# LvpeclTermWithCtrl.net
KiCad netlist of a schematic drawn in Altium Designer
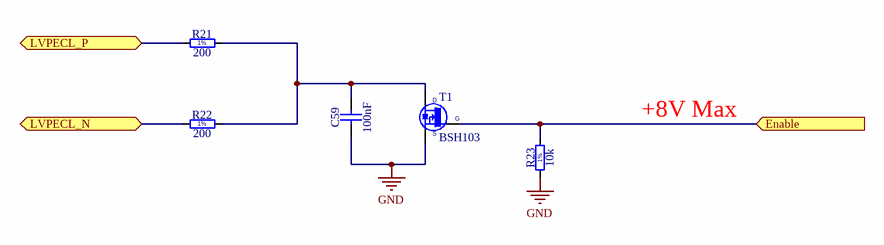
[diagram p0: LvpeclTermWithCtrl.SchDoc]

(export (version "E")
  (design (tool "Eeschema 10.0.6"))
  (components
    (comp (ref "C59")
      (value "100nF")
      (footprint "CAPC1005X55N")
      (description "Non-polarised capacitor")
      (fields
        (field (name "PART NUMBER") "CC0402_100NF_16V_10%_X7R")
        (field (name "VOLTAGE") "16V")
        (field (name "AUTHOR") "CERN DEM JLC")
      )
      (libsource (lib "Capacitors") (part "Capacitor - non polarized"))
    )
    (comp (ref "R21")
      (value "200")
      (footprint "RESC1005X40N")
      (description "Resistor - 1%")
      (fields
        (field (name "PART NUMBER") "R0402_200R_1%_0.0625W_100PPM")
        (field (name "POWER") "0.0625W")
        (field (name "AUTHOR") "CERN DEM JLC")
      )
      (libsource (lib "Resistors") (part "Resistor - 1%"))
    )
    (comp (ref "R22")
      (value "200")
      (footprint "RESC1005X40N")
      (description "Resistor - 1%")
      (fields
        (field (name "PART NUMBER") "R0402_200R_1%_0.0625W_100PPM")
        (field (name "POWER") "0.0625W")
        (field (name "AUTHOR") "CERN DEM JLC")
      )
      (libsource (lib "Resistors") (part "Resistor - 1%"))
    )
    (comp (ref "R23")
      (value "10k")
      (footprint "RESC1005X40N")
      (description "Resistor - 1%")
      (fields
        (field (name "PART NUMBER") "R0402_10K_1%_0.0625W_100PPM")
        (field (name "POWER") "0.0625W")
        (field (name "AUTHOR") "CERN DEM JLC")
      )
      (libsource (lib "Resistors") (part "Resistor - 1%"))
    )
    (comp (ref "T1")
      (value "BSH103")
      (footprint "SOT95P230X110-3N")
      (description "N-CHANNEL MOSFET WITH DIODE")
      (fields (field (name "MANUFACTURER") "NXP SEMICONDUCTORS") (field (name "AUTHOR") "CERN DEM JLC"))
      (libsource (lib "ICs And Semiconductors") (part "N-MOSFET-D 1G 2S 3D"))
    )
  )
  (nets
    (net (code "1") (name "/Enable") (class "Default")
      (node (ref "R23") (pin "2") (pinfunction "2_2") (pintype "passive"))
      (node (ref "T1") (pin "1") (pinfunction "G_1") (pintype "passive"))
    )
    (net (code "2") (name "/LVPECL_N") (class "Default")
      (node (ref "R22") (pin "1") (pinfunction "1_1") (pintype "passive"))
    )
    (net (code "3") (name "/LVPECL_P") (class "Default")
      (node (ref "R21") (pin "1") (pinfunction "1_1") (pintype "passive"))
    )
    (net (code "4") (name "GND") (class "Default")
      (node (ref "C59") (pin "1") (pinfunction "1_1") (pintype "passive"))
      (node (ref "R23") (pin "1") (pinfunction "1_1") (pintype "passive"))
      (node (ref "T1") (pin "2") (pinfunction "S_2") (pintype "passive"))
    )
    (net (code "5") (name "Net-(T1-D)") (class "Default")
      (node (ref "C59") (pin "2") (pinfunction "2_2") (pintype "passive"))
      (node (ref "R21") (pin "2") (pinfunction "2_2") (pintype "passive"))
      (node (ref "R22") (pin "2") (pinfunction "2_2") (pintype "passive"))
      (node (ref "T1") (pin "3") (pinfunction "D_3") (pintype "passive"))
    )
  )
)
